# power.net
KiCad netlist of a schematic drawn in EAGLE
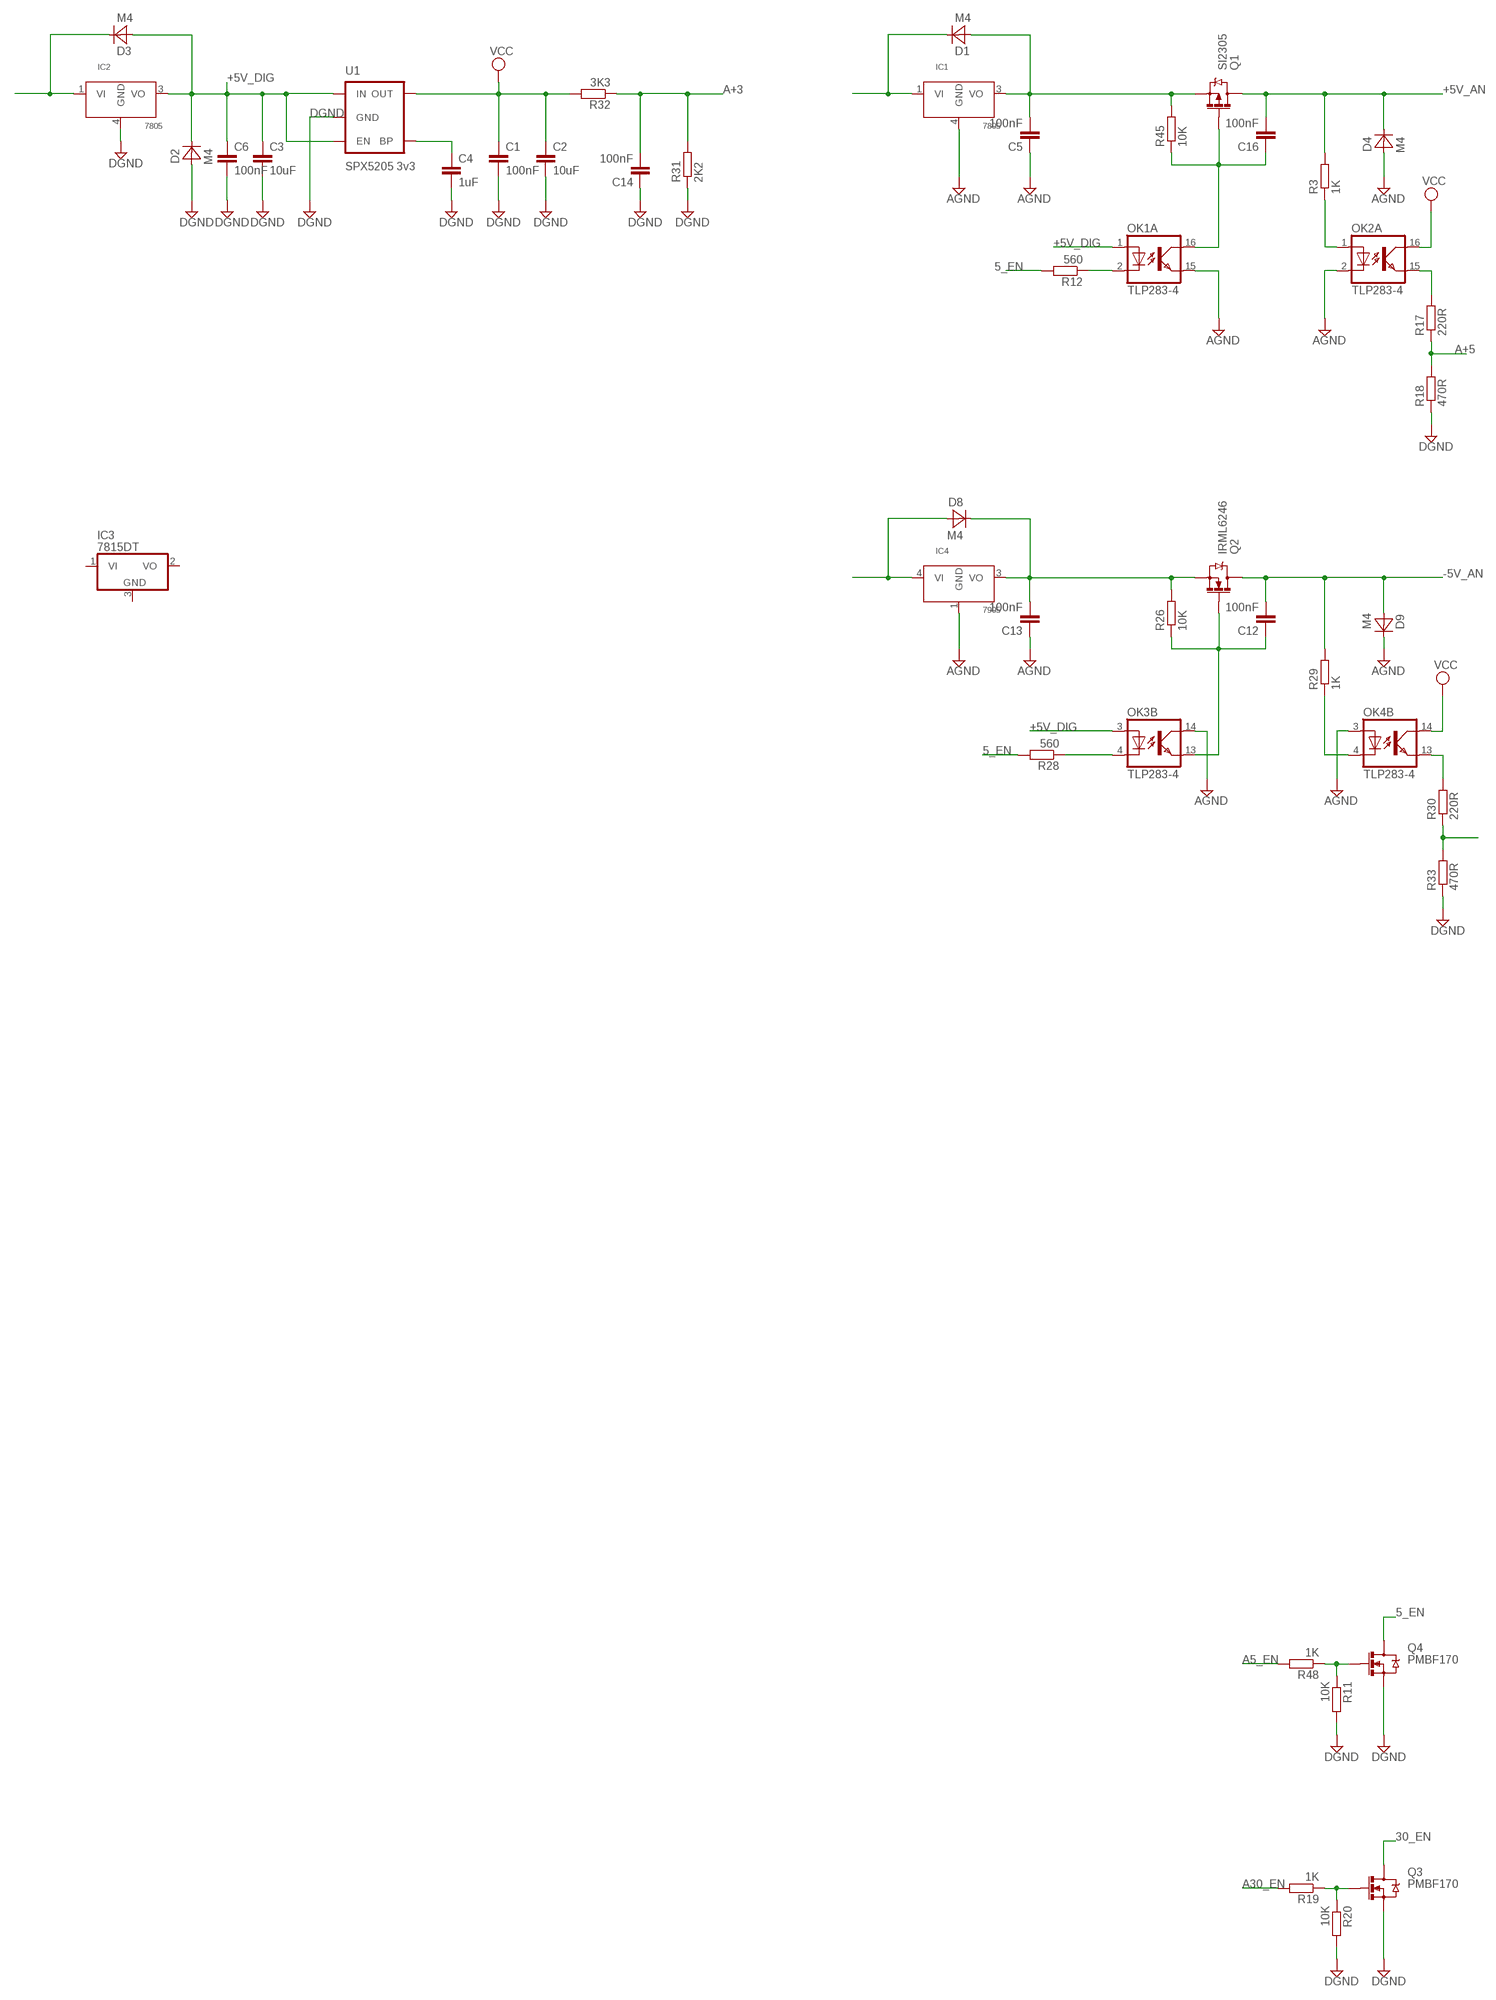
[diagram p0: schematic, sheet 1, part 1 of 2]
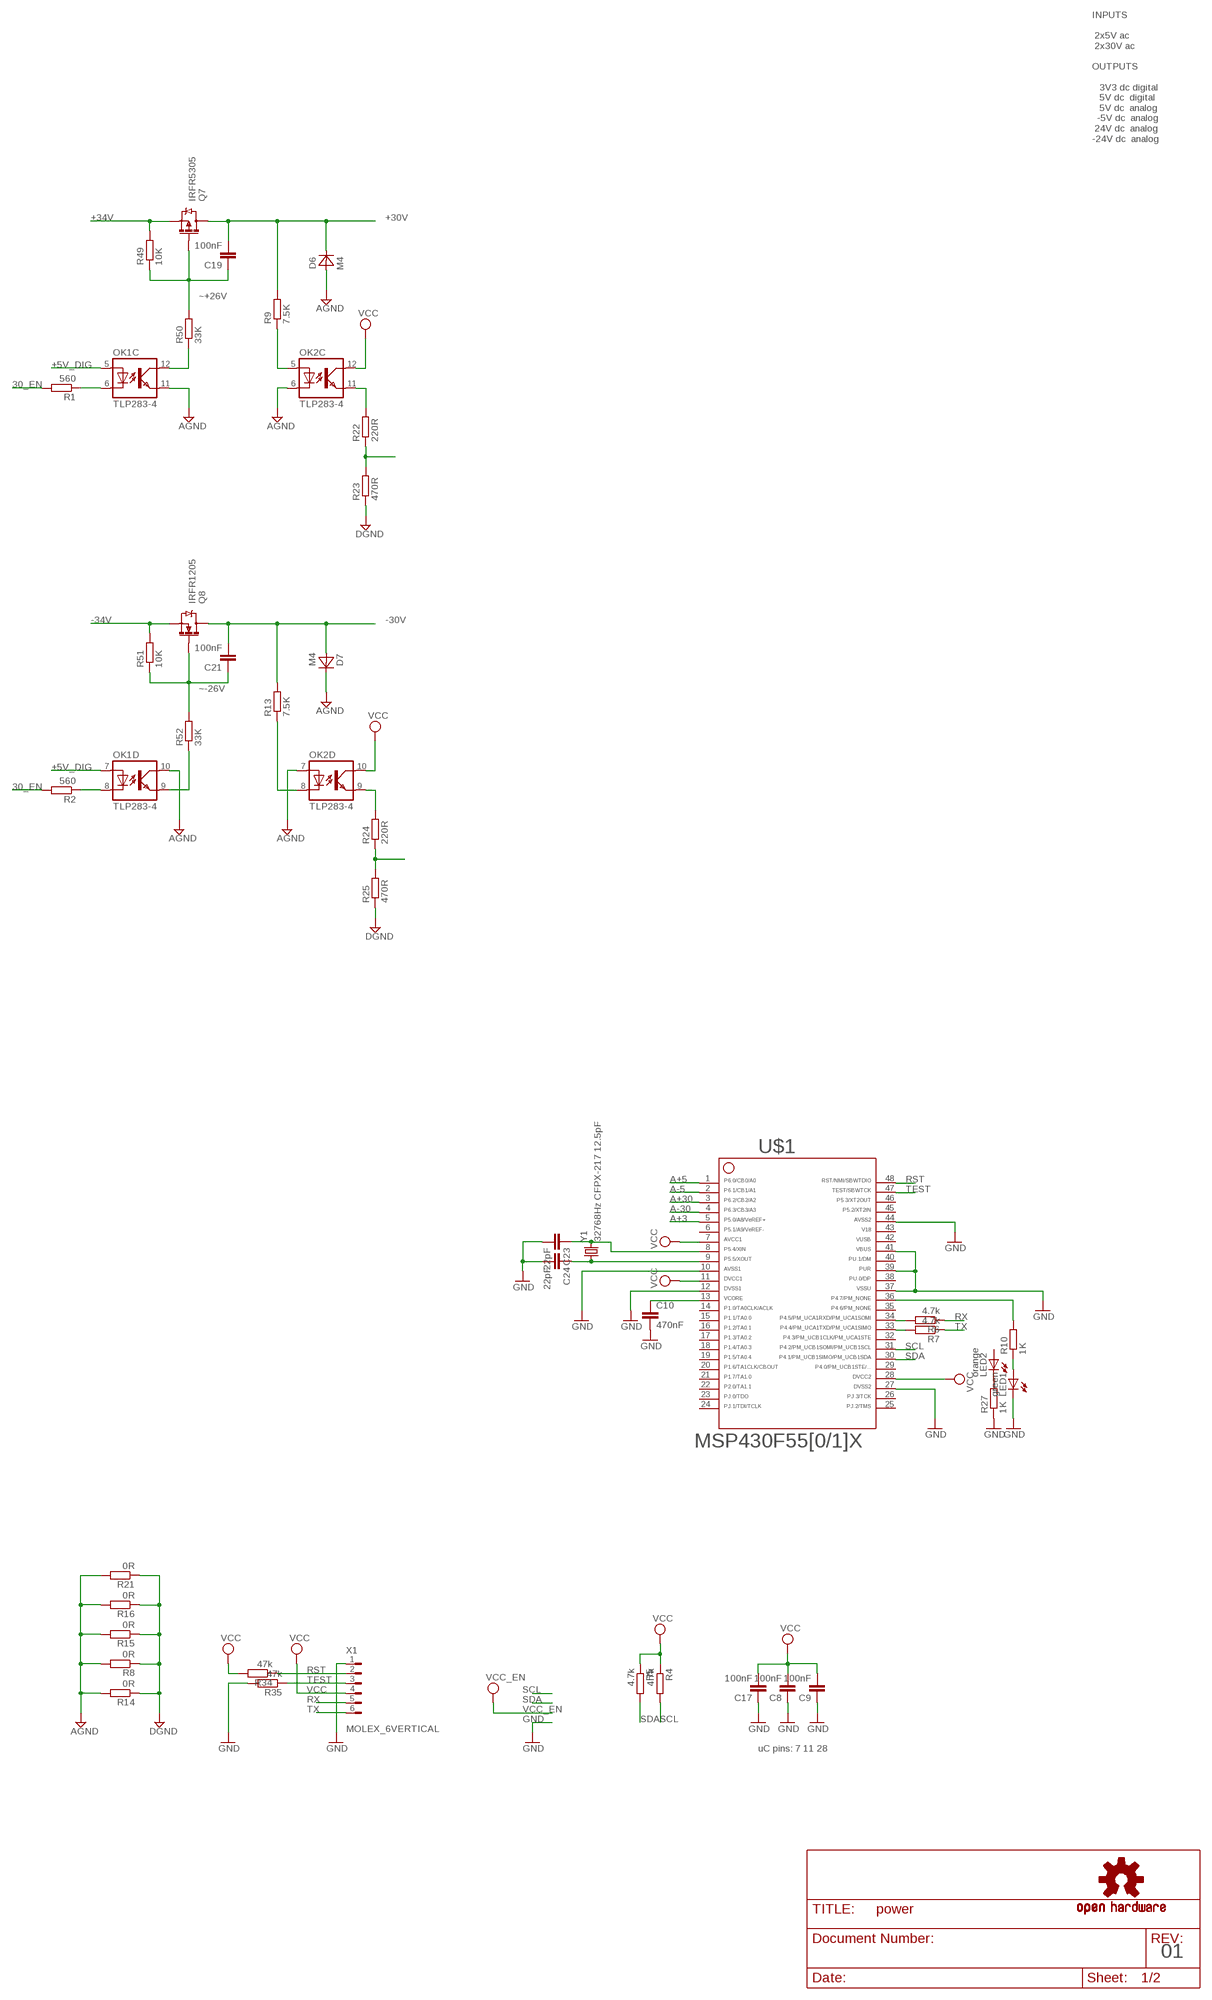
[diagram p1: schematic, sheet 1, part 2 of 2]

(export (version "E")
  (design (tool "Eeschema 10.0.6"))
  (components
    (comp (ref "C1")
      (value "100nF")
      (footprint "eagle-import:C0805")
      (libsource (lib "eagle-import") (part "C-EUC0805"))
    )
    (comp (ref "C2")
      (value "10uF")
      (footprint "eagle-import:C1206")
      (libsource (lib "eagle-import") (part "C-EUC1206"))
    )
    (comp (ref "C3")
      (value "10uF")
      (footprint "eagle-import:C1206")
      (libsource (lib "eagle-import") (part "C-EUC1206"))
    )
    (comp (ref "C4")
      (value "1uF")
      (footprint "eagle-import:C0805")
      (libsource (lib "eagle-import") (part "C-EUC0805"))
    )
    (comp (ref "C5")
      (value "100nF")
      (footprint "eagle-import:C0805")
      (libsource (lib "eagle-import") (part "C-EUC0805"))
    )
    (comp (ref "C6")
      (value "100nF")
      (footprint "eagle-import:C0805")
      (libsource (lib "eagle-import") (part "C-EUC0805"))
    )
    (comp (ref "C8")
      (value "100nF")
      (footprint "eagle-import:C0805")
      (libsource (lib "eagle-import") (part "C-EUC0805"))
    )
    (comp (ref "C9")
      (value "100nF")
      (footprint "eagle-import:C0805")
      (libsource (lib "eagle-import") (part "C-EUC0805"))
    )
    (comp (ref "C10")
      (value "470nF")
      (footprint "eagle-import:C0805")
      (libsource (lib "eagle-import") (part "C-EUC0805"))
    )
    (comp (ref "C12")
      (value "100nF")
      (footprint "eagle-import:C0805")
      (libsource (lib "eagle-import") (part "C-EUC0805"))
    )
    (comp (ref "C13")
      (value "100nF")
      (footprint "eagle-import:C0805")
      (libsource (lib "eagle-import") (part "C-EUC0805"))
    )
    (comp (ref "C14")
      (value "100nF")
      (footprint "eagle-import:C0805")
      (libsource (lib "eagle-import") (part "C-EUC0805"))
    )
    (comp (ref "C16")
      (value "100nF")
      (footprint "eagle-import:C0805")
      (libsource (lib "eagle-import") (part "C-EUC0805"))
    )
    (comp (ref "C17")
      (value "100nF")
      (footprint "eagle-import:C0805")
      (libsource (lib "eagle-import") (part "C-EUC0805"))
    )
    (comp (ref "C19")
      (value "100nF")
      (footprint "eagle-import:C0805")
      (libsource (lib "eagle-import") (part "C-EUC0805"))
    )
    (comp (ref "C21")
      (value "100nF")
      (footprint "eagle-import:C0805")
      (libsource (lib "eagle-import") (part "C-EUC0805"))
    )
    (comp (ref "C23")
      (value "22pF")
      (footprint "eagle-import:C0805")
      (libsource (lib "eagle-import") (part "C-EUC0805"))
    )
    (comp (ref "C24")
      (value "22pF")
      (footprint "eagle-import:C0805")
      (libsource (lib "eagle-import") (part "C-EUC0805"))
    )
    (comp (ref "D1")
      (value "M4")
      (footprint "eagle-import:SMA")
      (libsource (lib "eagle-import") (part "MBRA340T3"))
    )
    (comp (ref "D2")
      (value "M4")
      (footprint "eagle-import:SMA")
      (libsource (lib "eagle-import") (part "MBRA340T3"))
    )
    (comp (ref "D3")
      (value "M4")
      (footprint "eagle-import:SMA")
      (libsource (lib "eagle-import") (part "MBRA340T3"))
    )
    (comp (ref "D4")
      (value "M4")
      (footprint "eagle-import:SMA")
      (libsource (lib "eagle-import") (part "MBRA340T3"))
    )
    (comp (ref "D6")
      (value "M4")
      (footprint "eagle-import:SMA")
      (libsource (lib "eagle-import") (part "MBRA340T3"))
    )
    (comp (ref "D7")
      (value "M4")
      (footprint "eagle-import:SMA")
      (libsource (lib "eagle-import") (part "MBRA340T3"))
    )
    (comp (ref "D8")
      (value "M4")
      (footprint "eagle-import:SMA")
      (libsource (lib "eagle-import") (part "MBRA340T3"))
    )
    (comp (ref "D9")
      (value "M4")
      (footprint "eagle-import:SMA")
      (libsource (lib "eagle-import") (part "MBRA340T3"))
    )
    (comp (ref "IC1")
      (value "7805")
      (footprint "eagle-import:D2PACK")
      (libsource (lib "eagle-import") (part "78XX"))
    )
    (comp (ref "IC2")
      (value "7805")
      (footprint "eagle-import:D2PACK")
      (libsource (lib "eagle-import") (part "78XX"))
    )
    (comp (ref "IC3")
      (value "7815DT")
      (footprint "eagle-import:TO252")
      (libsource (lib "eagle-import") (part "78DT15"))
    )
    (comp (ref "IC4")
      (value "7905")
      (footprint "eagle-import:D2PACK")
      (libsource (lib "eagle-import") (part "79XX"))
    )
    (comp (ref "LED1")
      (value "green")
      (footprint "eagle-import:CHIP-LED0805")
      (libsource (lib "eagle-import") (part "LEDCHIP-LED0805"))
    )
    (comp (ref "LED2")
      (value "orange")
      (footprint "eagle-import:CHIP-LED0805")
      (libsource (lib "eagle-import") (part "LEDCHIP-LED0805"))
    )
    (comp (ref "OK1")
      (value "TLP283-4")
      (footprint "eagle-import:MINI-FLAT-16")
      (libsource (lib "eagle-import") (part "TLP283-4"))
    )
    (comp (ref "OK2")
      (value "TLP283-4")
      (footprint "eagle-import:MINI-FLAT-16")
      (libsource (lib "eagle-import") (part "TLP283-4"))
    )
    (comp (ref "OK3")
      (value "TLP283-4")
      (footprint "eagle-import:MINI-FLAT-16")
      (libsource (lib "eagle-import") (part "TLP283-4"))
    )
    (comp (ref "OK4")
      (value "TLP283-4")
      (footprint "eagle-import:MINI-FLAT-16")
      (libsource (lib "eagle-import") (part "TLP283-4"))
    )
    (comp (ref "Q1")
      (value "SI2305")
      (footprint "eagle-import:SOT23-3_POWER")
      (libsource (lib "eagle-import") (part "MOSFET-PCHANNEL_SOT23-3_POWER"))
    )
    (comp (ref "Q2")
      (value "IRML6246")
      (footprint "eagle-import:SOT23-3_POWER")
      (libsource (lib "eagle-import") (part "MOSFET-NCHANNEL_SOT23-3_POWER"))
    )
    (comp (ref "Q3")
      (value "PMBF170")
      (footprint "eagle-import:SOT23-3")
      (libsource (lib "eagle-import") (part "MOSFET-NCHANNEL_SOT23-3"))
    )
    (comp (ref "Q4")
      (value "PMBF170")
      (footprint "eagle-import:SOT23-3")
      (libsource (lib "eagle-import") (part "MOSFET-NCHANNEL_SOT23-3"))
    )
    (comp (ref "Q7")
      (value "IRFR5305")
      (footprint "eagle-import:D-PAK_TO252AA")
      (libsource (lib "eagle-import") (part "MOSFET-PCHANNEL_D-PAK"))
    )
    (comp (ref "Q8")
      (value "IRFR1205")
      (footprint "eagle-import:D-PAK_TO252AA")
      (libsource (lib "eagle-import") (part "MOSFET-NCHANNEL_D-PAK"))
    )
    (comp (ref "R1")
      (value "560")
      (footprint "eagle-import:R0805W")
      (libsource (lib "eagle-import") (part "R-EU_R0805W"))
    )
    (comp (ref "R2")
      (value "560")
      (footprint "eagle-import:R0805W")
      (libsource (lib "eagle-import") (part "R-EU_R0805W"))
    )
    (comp (ref "R3")
      (value "1K")
      (footprint "eagle-import:R0805W")
      (libsource (lib "eagle-import") (part "R-EU_R0805W"))
    )
    (comp (ref "R4")
      (value "4.7k")
      (footprint "eagle-import:R0805W")
      (libsource (lib "eagle-import") (part "R-EU_R0805W"))
    )
    (comp (ref "R5")
      (value "4.7k")
      (footprint "eagle-import:R0805W")
      (libsource (lib "eagle-import") (part "R-EU_R0805W"))
    )
    (comp (ref "R6")
      (value "4.7k")
      (footprint "eagle-import:R0805W")
      (libsource (lib "eagle-import") (part "R-EU_R0805W"))
    )
    (comp (ref "R7")
      (value "4.7k")
      (footprint "eagle-import:R0805W")
      (libsource (lib "eagle-import") (part "R-EU_R0805W"))
    )
    (comp (ref "R8")
      (value "0R")
      (footprint "eagle-import:R0805W")
      (libsource (lib "eagle-import") (part "R-EU_R0805W"))
    )
    (comp (ref "R9")
      (value "7.5K")
      (footprint "eagle-import:R0805W")
      (libsource (lib "eagle-import") (part "R-EU_R0805W"))
    )
    (comp (ref "R10")
      (value "1K")
      (footprint "eagle-import:R0805W")
      (libsource (lib "eagle-import") (part "R-EU_R0805W"))
    )
    (comp (ref "R11")
      (value "10K")
      (footprint "eagle-import:R0805W")
      (libsource (lib "eagle-import") (part "R-EU_R0805W"))
    )
    (comp (ref "R12")
      (value "560")
      (footprint "eagle-import:R0805W")
      (libsource (lib "eagle-import") (part "R-EU_R0805W"))
    )
    (comp (ref "R13")
      (value "7.5K")
      (footprint "eagle-import:R0805W")
      (libsource (lib "eagle-import") (part "R-EU_R0805W"))
    )
    (comp (ref "R14")
      (value "0R")
      (footprint "eagle-import:R0805W")
      (libsource (lib "eagle-import") (part "R-EU_R0805W"))
    )
    (comp (ref "R15")
      (value "0R")
      (footprint "eagle-import:R0805W")
      (libsource (lib "eagle-import") (part "R-EU_R0805W"))
    )
    (comp (ref "R16")
      (value "0R")
      (footprint "eagle-import:R0805W")
      (libsource (lib "eagle-import") (part "R-EU_R0805W"))
    )
    (comp (ref "R17")
      (value "220R")
      (footprint "eagle-import:R0805W")
      (libsource (lib "eagle-import") (part "R-EU_R0805W"))
    )
    (comp (ref "R18")
      (value "470R")
      (footprint "eagle-import:R0805W")
      (libsource (lib "eagle-import") (part "R-EU_R0805W"))
    )
    (comp (ref "R19")
      (value "1K")
      (footprint "eagle-import:R0805W")
      (libsource (lib "eagle-import") (part "R-EU_R0805W"))
    )
    (comp (ref "R20")
      (value "10K")
      (footprint "eagle-import:R0805W")
      (libsource (lib "eagle-import") (part "R-EU_R0805W"))
    )
    (comp (ref "R21")
      (value "0R")
      (footprint "eagle-import:R0805W")
      (libsource (lib "eagle-import") (part "R-EU_R0805W"))
    )
    (comp (ref "R22")
      (value "220R")
      (footprint "eagle-import:R0805W")
      (libsource (lib "eagle-import") (part "R-EU_R0805W"))
    )
    (comp (ref "R23")
      (value "470R")
      (footprint "eagle-import:R0805W")
      (libsource (lib "eagle-import") (part "R-EU_R0805W"))
    )
    (comp (ref "R24")
      (value "220R")
      (footprint "eagle-import:R0805W")
      (libsource (lib "eagle-import") (part "R-EU_R0805W"))
    )
    (comp (ref "R25")
      (value "470R")
      (footprint "eagle-import:R0805W")
      (libsource (lib "eagle-import") (part "R-EU_R0805W"))
    )
    (comp (ref "R26")
      (value "10K")
      (footprint "eagle-import:R0805W")
      (libsource (lib "eagle-import") (part "R-EU_R0805W"))
    )
    (comp (ref "R27")
      (value "1K")
      (footprint "eagle-import:R0805W")
      (libsource (lib "eagle-import") (part "R-EU_R0805W"))
    )
    (comp (ref "R28")
      (value "560")
      (footprint "eagle-import:R0805W")
      (libsource (lib "eagle-import") (part "R-EU_R0805W"))
    )
    (comp (ref "R29")
      (value "1K")
      (footprint "eagle-import:R0805W")
      (libsource (lib "eagle-import") (part "R-EU_R0805W"))
    )
    (comp (ref "R30")
      (value "220R")
      (footprint "eagle-import:R0805W")
      (libsource (lib "eagle-import") (part "R-EU_R0805W"))
    )
    (comp (ref "R31")
      (value "2K2")
      (footprint "eagle-import:R0805W")
      (libsource (lib "eagle-import") (part "R-EU_R0805W"))
    )
    (comp (ref "R32")
      (value "3K3")
      (footprint "eagle-import:R0805W")
      (libsource (lib "eagle-import") (part "R-EU_R0805W"))
    )
    (comp (ref "R33")
      (value "470R")
      (footprint "eagle-import:R0805W")
      (libsource (lib "eagle-import") (part "R-EU_R0805W"))
    )
    (comp (ref "R34")
      (value "47k")
      (footprint "eagle-import:R0805W")
      (libsource (lib "eagle-import") (part "R-EU_R0805W"))
    )
    (comp (ref "R35")
      (value "47k")
      (footprint "eagle-import:R0805W")
      (libsource (lib "eagle-import") (part "R-EU_R0805W"))
    )
    (comp (ref "R45")
      (value "10K")
      (footprint "eagle-import:R0805W")
      (libsource (lib "eagle-import") (part "R-EU_R0805W"))
    )
    (comp (ref "R48")
      (value "1K")
      (footprint "eagle-import:R0805W")
      (libsource (lib "eagle-import") (part "R-EU_R0805W"))
    )
    (comp (ref "R49")
      (value "10K")
      (footprint "eagle-import:R0805W")
      (libsource (lib "eagle-import") (part "R-EU_R0805W"))
    )
    (comp (ref "R50")
      (value "33K")
      (footprint "eagle-import:R0805W")
      (libsource (lib "eagle-import") (part "R-EU_R0805W"))
    )
    (comp (ref "R51")
      (value "10K")
      (footprint "eagle-import:R0805W")
      (libsource (lib "eagle-import") (part "R-EU_R0805W"))
    )
    (comp (ref "R52")
      (value "33K")
      (footprint "eagle-import:R0805W")
      (libsource (lib "eagle-import") (part "R-EU_R0805W"))
    )
    (comp (ref "U$1")
      (value "F55[0/1]X---PT48")
      (footprint "eagle-import:PT48")
      (libsource (lib "eagle-import") (part "F55[0/1]X---PT48"))
    )
    (comp (ref "U$7")
      (value "OSHW-LOGOM")
      (footprint "eagle-import:OSHW-LOGO-M")
      (libsource (lib "eagle-import") (part "OSHW-LOGOM"))
    )
    (comp (ref "U1")
      (value "SPX5205 3v3")
      (footprint "eagle-import:SOT23-5")
      (libsource (lib "eagle-import") (part "V_REG_LDOSMD"))
    )
    (comp (ref "X1")
      (value "MOLEX_6VERTICAL")
      (footprint "eagle-import:0530470610")
      (libsource (lib "eagle-import") (part "MOLEX_6VERTICAL"))
    )
    (comp (ref "Y1")
      (value "32768Hz CFPX-217 12.5pF")
      (footprint "eagle-import:CRYSTAL-SMD-3.2X1.5")
      (libsource (lib "eagle-import") (part "CRYSTAL3.2X1.5"))
    )
  )
  (nets
    (net (code "1") (name "+5V_AN") (class "Default")
      (node (ref "C16") (pin "2") (pinfunction "2_2") (pintype "passive"))
      (node (ref "D4") (pin "C") (pinfunction "C_C") (pintype "passive"))
      (node (ref "Q1") (pin "3") (pinfunction "D_3") (pintype "passive"))
      (node (ref "R3") (pin "2") (pinfunction "2_2") (pintype "passive"))
    )
    (net (code "2") (name "+5V_DIG") (class "Default")
      (node (ref "C3") (pin "1") (pinfunction "1_1") (pintype "passive"))
      (node (ref "C6") (pin "1") (pinfunction "1_1") (pintype "passive"))
      (node (ref "D2") (pin "C") (pinfunction "C_C") (pintype "passive"))
      (node (ref "D3") (pin "A") (pinfunction "A_A") (pintype "passive"))
      (node (ref "IC2") (pin "3") (pinfunction "VO_3") (pintype "bidirectional"))
      (node (ref "OK1") (pin "1") (pinfunction "A_1") (pintype "passive"))
      (node (ref "OK1") (pin "5") (pinfunction "A_5") (pintype "passive"))
      (node (ref "OK1") (pin "7") (pinfunction "A_7") (pintype "passive"))
      (node (ref "OK3") (pin "3") (pinfunction "A_3") (pintype "passive"))
      (node (ref "U1") (pin "1") (pinfunction "IN_1") (pintype "input"))
      (node (ref "U1") (pin "3") (pinfunction "EN_3") (pintype "input"))
    )
    (net (code "3") (name "+30V") (class "Default")
      (node (ref "C19") (pin "2") (pinfunction "2_2") (pintype "passive"))
      (node (ref "D6") (pin "C") (pinfunction "C_C") (pintype "passive"))
      (node (ref "Q7") (pin "2") (pinfunction "D_2") (pintype "passive"))
      (node (ref "R9") (pin "2") (pinfunction "2_2") (pintype "passive"))
    )
    (net (code "4") (name "-5V_AN") (class "Default")
      (node (ref "C12") (pin "2") (pinfunction "2_2") (pintype "passive"))
      (node (ref "D9") (pin "A") (pinfunction "A_A") (pintype "passive"))
      (node (ref "Q2") (pin "3") (pinfunction "D_3") (pintype "passive"))
      (node (ref "R29") (pin "2") (pinfunction "2_2") (pintype "passive"))
    )
    (net (code "5") (name "-30V") (class "Default")
      (node (ref "C21") (pin "2") (pinfunction "2_2") (pintype "passive"))
      (node (ref "D7") (pin "A") (pinfunction "A_A") (pintype "passive"))
      (node (ref "Q8") (pin "2") (pinfunction "D_2") (pintype "passive"))
      (node (ref "R13") (pin "2") (pinfunction "2_2") (pintype "passive"))
    )
    (net (code "6") (name "5_EN") (class "Default")
      (node (ref "Q4") (pin "3") (pinfunction "D_3") (pintype "passive"))
      (node (ref "R12") (pin "2") (pinfunction "2_2") (pintype "passive"))
      (node (ref "R28") (pin "2") (pinfunction "2_2") (pintype "passive"))
    )
    (net (code "7") (name "30_EN") (class "Default")
      (node (ref "Q3") (pin "3") (pinfunction "D_3") (pintype "passive"))
      (node (ref "R1") (pin "2") (pinfunction "2_2") (pintype "passive"))
      (node (ref "R2") (pin "2") (pinfunction "2_2") (pintype "passive"))
    )
    (net (code "8") (name "42") (class "Default")
      (node (ref "U$1") (pin "42") (pinfunction "42_42") (pintype "power_in"))
    )
    (net (code "9") (name "43") (class "Default")
      (node (ref "U$1") (pin "43") (pinfunction "43_43") (pintype "power_in"))
    )
    (net (code "10") (name "46") (class "Default")
      (node (ref "U$1") (pin "46") (pinfunction "46_46") (pintype "power_in"))
    )
    (net (code "11") (name "A+3") (class "Default")
      (node (ref "C14") (pin "2") (pinfunction "2_2") (pintype "passive"))
      (node (ref "R31") (pin "2") (pinfunction "2_2") (pintype "passive"))
      (node (ref "R32") (pin "1") (pinfunction "1_1") (pintype "passive"))
      (node (ref "U$1") (pin "5") (pinfunction "5_5") (pintype "bidirectional"))
    )
    (net (code "12") (name "A+5") (class "Default")
      (node (ref "R17") (pin "1") (pinfunction "1_1") (pintype "passive"))
      (node (ref "R18") (pin "2") (pinfunction "2_2") (pintype "passive"))
      (node (ref "U$1") (pin "1") (pinfunction "1_1") (pintype "bidirectional"))
    )
    (net (code "13") (name "A+30") (class "Default")
      (node (ref "U$1") (pin "3") (pinfunction "3_3") (pintype "bidirectional"))
    )
    (net (code "14") (name "A-5") (class "Default")
      (node (ref "U$1") (pin "2") (pinfunction "2_2") (pintype "bidirectional"))
    )
    (net (code "15") (name "A-30") (class "Default")
      (node (ref "U$1") (pin "4") (pinfunction "4_4") (pintype "bidirectional"))
    )
    (net (code "16") (name "A5_EN") (class "Default")
      (node (ref "R48") (pin "2") (pinfunction "2_2") (pintype "passive"))
    )
    (net (code "17") (name "A30_EN") (class "Default")
      (node (ref "R19") (pin "2") (pinfunction "2_2") (pintype "passive"))
    )
    (net (code "18") (name "AGND") (class "Default")
      (node (ref "C13") (pin "1") (pinfunction "1_1") (pintype "passive"))
      (node (ref "C5") (pin "1") (pinfunction "1_1") (pintype "passive"))
      (node (ref "D4") (pin "A") (pinfunction "A_A") (pintype "passive"))
      (node (ref "D6") (pin "A") (pinfunction "A_A") (pintype "passive"))
      (node (ref "D7") (pin "C") (pinfunction "C_C") (pintype "passive"))
      (node (ref "D9") (pin "C") (pinfunction "C_C") (pintype "passive"))
      (node (ref "IC1") (pin "4") (pinfunction "GND_4") (pintype "bidirectional"))
      (node (ref "IC4") (pin "1") (pinfunction "GND_1") (pintype "bidirectional"))
      (node (ref "OK1") (pin "10") (pinfunction "COL_10") (pintype "passive"))
      (node (ref "OK1") (pin "11") (pinfunction "EMIT_11") (pintype "passive"))
      (node (ref "OK1") (pin "15") (pinfunction "EMIT_15") (pintype "passive"))
      (node (ref "OK2") (pin "2") (pinfunction "C_2") (pintype "passive"))
      (node (ref "OK2") (pin "6") (pinfunction "C_6") (pintype "passive"))
      (node (ref "OK2") (pin "7") (pinfunction "A_7") (pintype "passive"))
      (node (ref "OK3") (pin "14") (pinfunction "COL_14") (pintype "passive"))
      (node (ref "OK4") (pin "3") (pinfunction "A_3") (pintype "passive"))
      (node (ref "R14") (pin "2") (pinfunction "2_2") (pintype "passive"))
      (node (ref "R15") (pin "2") (pinfunction "2_2") (pintype "passive"))
      (node (ref "R16") (pin "2") (pinfunction "2_2") (pintype "passive"))
      (node (ref "R21") (pin "2") (pinfunction "2_2") (pintype "passive"))
      (node (ref "R8") (pin "2") (pinfunction "2_2") (pintype "passive"))
    )
    (net (code "19") (name "DGND") (class "Default")
      (node (ref "C1") (pin "2") (pinfunction "2_2") (pintype "passive"))
      (node (ref "C14") (pin "1") (pinfunction "1_1") (pintype "passive"))
      (node (ref "C2") (pin "2") (pinfunction "2_2") (pintype "passive"))
      (node (ref "C3") (pin "2") (pinfunction "2_2") (pintype "passive"))
      (node (ref "C4") (pin "2") (pinfunction "2_2") (pintype "passive"))
      (node (ref "C6") (pin "2") (pinfunction "2_2") (pintype "passive"))
      (node (ref "D2") (pin "A") (pinfunction "A_A") (pintype "passive"))
      (node (ref "IC2") (pin "4") (pinfunction "GND_4") (pintype "bidirectional"))
      (node (ref "Q3") (pin "2") (pinfunction "S_2") (pintype "passive"))
      (node (ref "Q4") (pin "2") (pinfunction "S_2") (pintype "passive"))
      (node (ref "R11") (pin "2") (pinfunction "2_2") (pintype "passive"))
      (node (ref "R14") (pin "1") (pinfunction "1_1") (pintype "passive"))
      (node (ref "R15") (pin "1") (pinfunction "1_1") (pintype "passive"))
      (node (ref "R16") (pin "1") (pinfunction "1_1") (pintype "passive"))
      (node (ref "R18") (pin "1") (pinfunction "1_1") (pintype "passive"))
      (node (ref "R20") (pin "2") (pinfunction "2_2") (pintype "passive"))
      (node (ref "R21") (pin "1") (pinfunction "1_1") (pintype "passive"))
      (node (ref "R23") (pin "1") (pinfunction "1_1") (pintype "passive"))
      (node (ref "R25") (pin "1") (pinfunction "1_1") (pintype "passive"))
      (node (ref "R31") (pin "1") (pinfunction "1_1") (pintype "passive"))
      (node (ref "R33") (pin "1") (pinfunction "1_1") (pintype "passive"))
      (node (ref "R8") (pin "1") (pinfunction "1_1") (pintype "passive"))
      (node (ref "U1") (pin "2") (pinfunction "GND_2") (pintype "input"))
    )
    (net (code "20") (name "GND") (class "Default")
      (node (ref "C10") (pin "2") (pinfunction "2_2") (pintype "passive"))
      (node (ref "C17") (pin "1") (pinfunction "1_1") (pintype "passive"))
      (node (ref "C23") (pin "2") (pinfunction "2_2") (pintype "passive"))
      (node (ref "C24") (pin "2") (pinfunction "2_2") (pintype "passive"))
      (node (ref "C8") (pin "1") (pinfunction "1_1") (pintype "passive"))
      (node (ref "C9") (pin "1") (pinfunction "1_1") (pintype "passive"))
      (node (ref "LED1") (pin "C") (pinfunction "C_C") (pintype "passive"))
      (node (ref "R27") (pin "1") (pinfunction "1_1") (pintype "passive"))
      (node (ref "R35") (pin "2") (pinfunction "2_2") (pintype "passive"))
      (node (ref "U$1") (pin "10") (pinfunction "10_10") (pintype "power_in"))
      (node (ref "U$1") (pin "12") (pinfunction "12_12") (pintype "power_in"))
      (node (ref "U$1") (pin "27") (pinfunction "27_27") (pintype "power_in"))
      (node (ref "U$1") (pin "37") (pinfunction "37_37") (pintype "power_in"))
      (node (ref "U$1") (pin "39") (pinfunction "39_39") (pintype "bidirectional"))
      (node (ref "U$1") (pin "41") (pinfunction "41_41") (pintype "power_in"))
      (node (ref "U$1") (pin "44") (pinfunction "44_44") (pintype "power_in"))
      (node (ref "X1") (pin "1") (pinfunction "1_1") (pintype "passive"))
    )
    (net (code "21") (name "Net-(C10-Pad1)") (class "Default")
      (node (ref "C10") (pin "1") (pinfunction "1_1") (pintype "passive"))
      (node (ref "U$1") (pin "13") (pinfunction "13_13") (pintype "power_in"))
    )
    (net (code "22") (name "Net-(IC1-VI)") (class "Default")
      (node (ref "D1") (pin "C") (pinfunction "C_C") (pintype "passive"))
      (node (ref "IC1") (pin "1") (pinfunction "VI_1") (pintype "bidirectional"))
    )
    (net (code "23") (name "Net-(IC1-VO)") (class "Default")
      (node (ref "C5") (pin "2") (pinfunction "2_2") (pintype "passive"))
      (node (ref "D1") (pin "A") (pinfunction "A_A") (pintype "passive"))
      (node (ref "IC1") (pin "3") (pinfunction "VO_3") (pintype "bidirectional"))
      (node (ref "Q1") (pin "2") (pinfunction "S_2") (pintype "passive"))
      (node (ref "R45") (pin "2") (pinfunction "2_2") (pintype "passive"))
    )
    (net (code "24") (name "Net-(IC2-VI)") (class "Default")
      (node (ref "D3") (pin "C") (pinfunction "C_C") (pintype "passive"))
      (node (ref "IC2") (pin "1") (pinfunction "VI_1") (pintype "bidirectional"))
    )
    (net (code "25") (name "Net-(IC4-VI)") (class "Default")
      (node (ref "D8") (pin "A") (pinfunction "A_A") (pintype "passive"))
      (node (ref "IC4") (pin "4") (pinfunction "VI_4") (pintype "bidirectional"))
    )
    (net (code "26") (name "Net-(IC4-VO)") (class "Default")
      (node (ref "C13") (pin "2") (pinfunction "2_2") (pintype "passive"))
      (node (ref "D8") (pin "C") (pinfunction "C_C") (pintype "passive"))
      (node (ref "IC4") (pin "3") (pinfunction "VO_3") (pintype "bidirectional"))
      (node (ref "Q2") (pin "2") (pinfunction "S_2") (pintype "passive"))
      (node (ref "R26") (pin "2") (pinfunction "2_2") (pintype "passive"))
    )
    (net (code "27") (name "Net-(LED1-PadA)") (class "Default")
      (node (ref "LED1") (pin "A") (pinfunction "A_A") (pintype "passive"))
      (node (ref "R10") (pin "1") (pinfunction "1_1") (pintype "passive"))
    )
    (net (code "28") (name "Net-(LED2-PadC)") (class "Default")
      (node (ref "LED2") (pin "C") (pinfunction "C_C") (pintype "passive"))
      (node (ref "R27") (pin "2") (pinfunction "2_2") (pintype "passive"))
    )
    (net (code "29") (name "Net-(OK1A-C)") (class "Default")
      (node (ref "OK1") (pin "2") (pinfunction "C_2") (pintype "passive"))
      (node (ref "R12") (pin "1") (pinfunction "1_1") (pintype "passive"))
    )
    (net (code "30") (name "Net-(OK1A-COL)") (class "Default")
      (node (ref "C16") (pin "1") (pinfunction "1_1") (pintype "passive"))
      (node (ref "OK1") (pin "16") (pinfunction "COL_16") (pintype "passive"))
      (node (ref "Q1") (pin "1") (pinfunction "G_1") (pintype "passive"))
      (node (ref "R45") (pin "1") (pinfunction "1_1") (pintype "passive"))
    )
    (net (code "31") (name "Net-(OK1C-C)") (class "Default")
      (node (ref "OK1") (pin "6") (pinfunction "C_6") (pintype "passive"))
      (node (ref "R1") (pin "1") (pinfunction "1_1") (pintype "passive"))
    )
    (net (code "32") (name "Net-(OK1C-COL)") (class "Default")
      (node (ref "OK1") (pin "12") (pinfunction "COL_12") (pintype "passive"))
      (node (ref "R50") (pin "1") (pinfunction "1_1") (pintype "passive"))
    )
    (net (code "33") (name "Net-(OK1D-C)") (class "Default")
      (node (ref "OK1") (pin "8") (pinfunction "C_8") (pintype "passive"))
      (node (ref "R2") (pin "1") (pinfunction "1_1") (pintype "passive"))
    )
    (net (code "34") (name "Net-(OK1D-EMIT)") (class "Default")
      (node (ref "OK1") (pin "9") (pinfunction "EMIT_9") (pintype "passive"))
      (node (ref "R52") (pin "1") (pinfunction "1_1") (pintype "passive"))
    )
    (net (code "35") (name "Net-(OK2A-A)") (class "Default")
      (node (ref "OK2") (pin "1") (pinfunction "A_1") (pintype "passive"))
      (node (ref "R3") (pin "1") (pinfunction "1_1") (pintype "passive"))
    )
    (net (code "36") (name "Net-(OK2A-EMIT)") (class "Default")
      (node (ref "OK2") (pin "15") (pinfunction "EMIT_15") (pintype "passive"))
      (node (ref "R17") (pin "2") (pinfunction "2_2") (pintype "passive"))
    )
    (net (code "37") (name "Net-(OK2C-A)") (class "Default")
      (node (ref "OK2") (pin "5") (pinfunction "A_5") (pintype "passive"))
      (node (ref "R9") (pin "1") (pinfunction "1_1") (pintype "passive"))
    )
    (net (code "38") (name "Net-(OK2C-EMIT)") (class "Default")
      (node (ref "OK2") (pin "11") (pinfunction "EMIT_11") (pintype "passive"))
      (node (ref "R22") (pin "2") (pinfunction "2_2") (pintype "passive"))
    )
    (net (code "39") (name "Net-(OK2D-C)") (class "Default")
      (node (ref "OK2") (pin "8") (pinfunction "C_8") (pintype "passive"))
      (node (ref "R13") (pin "1") (pinfunction "1_1") (pintype "passive"))
    )
    (net (code "40") (name "Net-(OK2D-EMIT)") (class "Default")
      (node (ref "OK2") (pin "9") (pinfunction "EMIT_9") (pintype "passive"))
      (node (ref "R24") (pin "2") (pinfunction "2_2") (pintype "passive"))
    )
    (net (code "41") (name "Net-(OK3B-C)") (class "Default")
      (node (ref "OK3") (pin "4") (pinfunction "C_4") (pintype "passive"))
      (node (ref "R28") (pin "1") (pinfunction "1_1") (pintype "passive"))
    )
    (net (code "42") (name "Net-(OK3B-EMIT)") (class "Default")
      (node (ref "C12") (pin "1") (pinfunction "1_1") (pintype "passive"))
      (node (ref "OK3") (pin "13") (pinfunction "EMIT_13") (pintype "passive"))
      (node (ref "Q2") (pin "1") (pinfunction "G_1") (pintype "passive"))
      (node (ref "R26") (pin "1") (pinfunction "1_1") (pintype "passive"))
    )
    (net (code "43") (name "Net-(OK4B-C)") (class "Default")
      (node (ref "OK4") (pin "4") (pinfunction "C_4") (pintype "passive"))
      (node (ref "R29") (pin "1") (pinfunction "1_1") (pintype "passive"))
    )
    (net (code "44") (name "Net-(OK4B-EMIT)") (class "Default")
      (node (ref "OK4") (pin "13") (pinfunction "EMIT_13") (pintype "passive"))
      (node (ref "R30") (pin "2") (pinfunction "2_2") (pintype "passive"))
    )
    (net (code "45") (name "Net-(Q3-G)") (class "Default")
      (node (ref "Q3") (pin "1") (pinfunction "G_1") (pintype "passive"))
      (node (ref "R19") (pin "1") (pinfunction "1_1") (pintype "passive"))
      (node (ref "R20") (pin "1") (pinfunction "1_1") (pintype "passive"))
    )
    (net (code "46") (name "Net-(Q4-G)") (class "Default")
      (node (ref "Q4") (pin "1") (pinfunction "G_1") (pintype "passive"))
      (node (ref "R11") (pin "1") (pinfunction "1_1") (pintype "passive"))
      (node (ref "R48") (pin "1") (pinfunction "1_1") (pintype "passive"))
    )
    (net (code "47") (name "Net-(Q7-G)") (class "Default")
      (node (ref "C19") (pin "1") (pinfunction "1_1") (pintype "passive"))
      (node (ref "Q7") (pin "1") (pinfunction "G_1") (pintype "passive"))
      (node (ref "R49") (pin "1") (pinfunction "1_1") (pintype "passive"))
      (node (ref "R50") (pin "2") (pinfunction "2_2") (pintype "passive"))
    )
    (net (code "48") (name "Net-(Q7-S)") (class "Default")
      (node (ref "Q7") (pin "3") (pinfunction "S_3") (pintype "passive"))
      (node (ref "R49") (pin "2") (pinfunction "2_2") (pintype "passive"))
    )
    (net (code "49") (name "Net-(Q8-G)") (class "Default")
      (node (ref "C21") (pin "1") (pinfunction "1_1") (pintype "passive"))
      (node (ref "Q8") (pin "1") (pinfunction "G_1") (pintype "passive"))
      (node (ref "R51") (pin "1") (pinfunction "1_1") (pintype "passive"))
      (node (ref "R52") (pin "2") (pinfunction "2_2") (pintype "passive"))
    )
    (net (code "50") (name "Net-(Q8-S)") (class "Default")
      (node (ref "Q8") (pin "3") (pinfunction "S_3") (pintype "passive"))
      (node (ref "R51") (pin "2") (pinfunction "2_2") (pintype "passive"))
    )
    (net (code "51") (name "Net-(R6-Pad2)") (class "Default")
      (node (ref "R6") (pin "2") (pinfunction "2_2") (pintype "passive"))
      (node (ref "U$1") (pin "34") (pinfunction "34_34") (pintype "bidirectional"))
    )
    (net (code "52") (name "Net-(R7-Pad2)") (class "Default")
      (node (ref "R7") (pin "2") (pinfunction "2_2") (pintype "passive"))
      (node (ref "U$1") (pin "33") (pinfunction "33_33") (pintype "bidirectional"))
    )
    (net (code "53") (name "Net-(R10-Pad2)") (class "Default")
      (node (ref "R10") (pin "2") (pinfunction "2_2") (pintype "passive"))
      (node (ref "U$1") (pin "36") (pinfunction "36_36") (pintype "bidirectional"))
    )
    (net (code "54") (name "Net-(R22-Pad1)") (class "Default")
      (node (ref "R22") (pin "1") (pinfunction "1_1") (pintype "passive"))
      (node (ref "R23") (pin "2") (pinfunction "2_2") (pintype "passive"))
    )
    (net (code "55") (name "Net-(R24-Pad1)") (class "Default")
      (node (ref "R24") (pin "1") (pinfunction "1_1") (pintype "passive"))
      (node (ref "R25") (pin "2") (pinfunction "2_2") (pintype "passive"))
    )
    (net (code "56") (name "Net-(R30-Pad1)") (class "Default")
      (node (ref "R30") (pin "1") (pinfunction "1_1") (pintype "passive"))
      (node (ref "R33") (pin "2") (pinfunction "2_2") (pintype "passive"))
    )
    (net (code "57") (name "Net-(U1-BP)") (class "Default")
      (node (ref "C4") (pin "1") (pinfunction "1_1") (pintype "passive"))
      (node (ref "U1") (pin "4") (pinfunction "BP_4") (pintype "input"))
    )
    (net (code "58") (name "Net-(Y1-1)") (class "Default")
      (node (ref "C24") (pin "1") (pinfunction "1_1") (pintype "passive"))
      (node (ref "U$1") (pin "9") (pinfunction "9_9") (pintype "bidirectional"))
      (node (ref "Y1") (pin "P$1") (pinfunction "1_P$1") (pintype "passive"))
    )
    (net (code "59") (name "Net-(Y1-2)") (class "Default")
      (node (ref "C23") (pin "1") (pinfunction "1_1") (pintype "passive"))
      (node (ref "U$1") (pin "8") (pinfunction "8_8") (pintype "bidirectional"))
      (node (ref "Y1") (pin "P$2") (pinfunction "2_P$2") (pintype "passive"))
    )
    (net (code "60") (name "RST") (class "Default")
      (node (ref "R34") (pin "1") (pinfunction "1_1") (pintype "passive"))
      (node (ref "U$1") (pin "48") (pinfunction "48_48") (pintype "bidirectional"))
      (node (ref "X1") (pin "2") (pinfunction "2_2") (pintype "passive"))
    )
    (net (code "61") (name "RX") (class "Default")
      (node (ref "R6") (pin "1") (pinfunction "1_1") (pintype "passive"))
      (node (ref "X1") (pin "5") (pinfunction "5_5") (pintype "passive"))
    )
    (net (code "62") (name "SCL") (class "Default")
      (node (ref "R4") (pin "2") (pinfunction "2_2") (pintype "passive"))
      (node (ref "U$1") (pin "31") (pinfunction "31_31") (pintype "bidirectional"))
    )
    (net (code "63") (name "SDA") (class "Default")
      (node (ref "R5") (pin "2") (pinfunction "2_2") (pintype "passive"))
      (node (ref "U$1") (pin "30") (pinfunction "30_30") (pintype "bidirectional"))
    )
    (net (code "64") (name "TEST") (class "Default")
      (node (ref "R35") (pin "1") (pinfunction "1_1") (pintype "passive"))
      (node (ref "U$1") (pin "47") (pinfunction "47_47") (pintype "input"))
      (node (ref "X1") (pin "3") (pinfunction "3_3") (pintype "passive"))
    )
    (net (code "65") (name "TX") (class "Default")
      (node (ref "R7") (pin "1") (pinfunction "1_1") (pintype "passive"))
      (node (ref "X1") (pin "6") (pinfunction "6_6") (pintype "passive"))
    )
    (net (code "66") (name "VCC") (class "Default")
      (node (ref "C1") (pin "1") (pinfunction "1_1") (pintype "passive"))
      (node (ref "C17") (pin "2") (pinfunction "2_2") (pintype "passive"))
      (node (ref "C2") (pin "1") (pinfunction "1_1") (pintype "passive"))
      (node (ref "C8") (pin "2") (pinfunction "2_2") (pintype "passive"))
      (node (ref "C9") (pin "2") (pinfunction "2_2") (pintype "passive"))
      (node (ref "OK2") (pin "10") (pinfunction "COL_10") (pintype "passive"))
      (node (ref "OK2") (pin "12") (pinfunction "COL_12") (pintype "passive"))
      (node (ref "OK2") (pin "16") (pinfunction "COL_16") (pintype "passive"))
      (node (ref "OK4") (pin "14") (pinfunction "COL_14") (pintype "passive"))
      (node (ref "R32") (pin "2") (pinfunction "2_2") (pintype "passive"))
      (node (ref "R34") (pin "2") (pinfunction "2_2") (pintype "passive"))
      (node (ref "R4") (pin "1") (pinfunction "1_1") (pintype "passive"))
      (node (ref "R5") (pin "1") (pinfunction "1_1") (pintype "passive"))
      (node (ref "U$1") (pin "11") (pinfunction "11_11") (pintype "power_in"))
      (node (ref "U$1") (pin "28") (pinfunction "28_28") (pintype "power_in"))
      (node (ref "U$1") (pin "7") (pinfunction "7_7") (pintype "power_in"))
      (node (ref "U1") (pin "5") (pinfunction "OUT_5") (pintype "passive"))
      (node (ref "X1") (pin "4") (pinfunction "4_4") (pintype "passive"))
    )
    (net (code "68") (name "unconnected-(IC3-GND-Pad3)") (class "Default")
      (node (ref "IC3") (pin "3") (pinfunction "GND_3") (pintype "passive"))
    )
    (net (code "69") (name "unconnected-(IC3-VI-Pad1)") (class "Default")
      (node (ref "IC3") (pin "1") (pinfunction "VI_1") (pintype "input"))
    )
    (net (code "70") (name "unconnected-(IC3-VO-Pad2)") (class "Default")
      (node (ref "IC3") (pin "2") (pinfunction "VO_2") (pintype "passive"))
    )
    (net (code "71") (name "unconnected-(LED2-PadA)") (class "Default")
      (node (ref "LED2") (pin "A") (pinfunction "A_A") (pintype "passive"))
    )
    (net (code "72") (name "unconnected-(U$1-Pad6)") (class "Default")
      (node (ref "U$1") (pin "6") (pinfunction "6_6") (pintype "bidirectional"))
    )
    (net (code "73") (name "unconnected-(U$1-Pad14)") (class "Default")
      (node (ref "U$1") (pin "14") (pinfunction "14_14") (pintype "bidirectional"))
    )
    (net (code "74") (name "unconnected-(U$1-Pad15)") (class "Default")
      (node (ref "U$1") (pin "15") (pinfunction "15_15") (pintype "bidirectional"))
    )
    (net (code "75") (name "unconnected-(U$1-Pad16)") (class "Default")
      (node (ref "U$1") (pin "16") (pinfunction "16_16") (pintype "bidirectional"))
    )
    (net (code "76") (name "unconnected-(U$1-Pad17)") (class "Default")
      (node (ref "U$1") (pin "17") (pinfunction "17_17") (pintype "bidirectional"))
    )
    (net (code "77") (name "unconnected-(U$1-Pad18)") (class "Default")
      (node (ref "U$1") (pin "18") (pinfunction "18_18") (pintype "bidirectional"))
    )
    (net (code "78") (name "unconnected-(U$1-Pad19)") (class "Default")
      (node (ref "U$1") (pin "19") (pinfunction "19_19") (pintype "bidirectional"))
    )
    (net (code "79") (name "unconnected-(U$1-Pad20)") (class "Default")
      (node (ref "U$1") (pin "20") (pinfunction "20_20") (pintype "bidirectional"))
    )
    (net (code "80") (name "unconnected-(U$1-Pad21)") (class "Default")
      (node (ref "U$1") (pin "21") (pinfunction "21_21") (pintype "bidirectional"))
    )
    (net (code "81") (name "unconnected-(U$1-Pad22)") (class "Default")
      (node (ref "U$1") (pin "22") (pinfunction "22_22") (pintype "bidirectional"))
    )
    (net (code "82") (name "unconnected-(U$1-Pad23)") (class "Default")
      (node (ref "U$1") (pin "23") (pinfunction "23_23") (pintype "bidirectional"))
    )
    (net (code "83") (name "unconnected-(U$1-Pad24)") (class "Default")
      (node (ref "U$1") (pin "24") (pinfunction "24_24") (pintype "bidirectional"))
    )
    (net (code "84") (name "unconnected-(U$1-Pad25)") (class "Default")
      (node (ref "U$1") (pin "25") (pinfunction "25_25") (pintype "bidirectional"))
    )
    (net (code "85") (name "unconnected-(U$1-Pad26)") (class "Default")
      (node (ref "U$1") (pin "26") (pinfunction "26_26") (pintype "bidirectional"))
    )
    (net (code "86") (name "unconnected-(U$1-Pad29)") (class "Default")
      (node (ref "U$1") (pin "29") (pinfunction "29_29") (pintype "bidirectional"))
    )
    (net (code "87") (name "unconnected-(U$1-Pad32)") (class "Default")
      (node (ref "U$1") (pin "32") (pinfunction "32_32") (pintype "bidirectional"))
    )
    (net (code "88") (name "unconnected-(U$1-Pad35)") (class "Default")
      (node (ref "U$1") (pin "35") (pinfunction "35_35") (pintype "bidirectional"))
    )
    (net (code "89") (name "unconnected-(U$1-Pad38)") (class "Default")
      (node (ref "U$1") (pin "38") (pinfunction "38_38") (pintype "bidirectional"))
    )
    (net (code "90") (name "unconnected-(U$1-Pad40)") (class "Default")
      (node (ref "U$1") (pin "40") (pinfunction "40_40") (pintype "bidirectional"))
    )
    (net (code "91") (name "unconnected-(U$1-Pad45)") (class "Default")
      (node (ref "U$1") (pin "45") (pinfunction "45_45") (pintype "bidirectional"))
    )
  )
)
